# ATmega324PB_Xplained_Pro_Target_MCU.net
KiCad netlist of a schematic drawn in Altium Designer
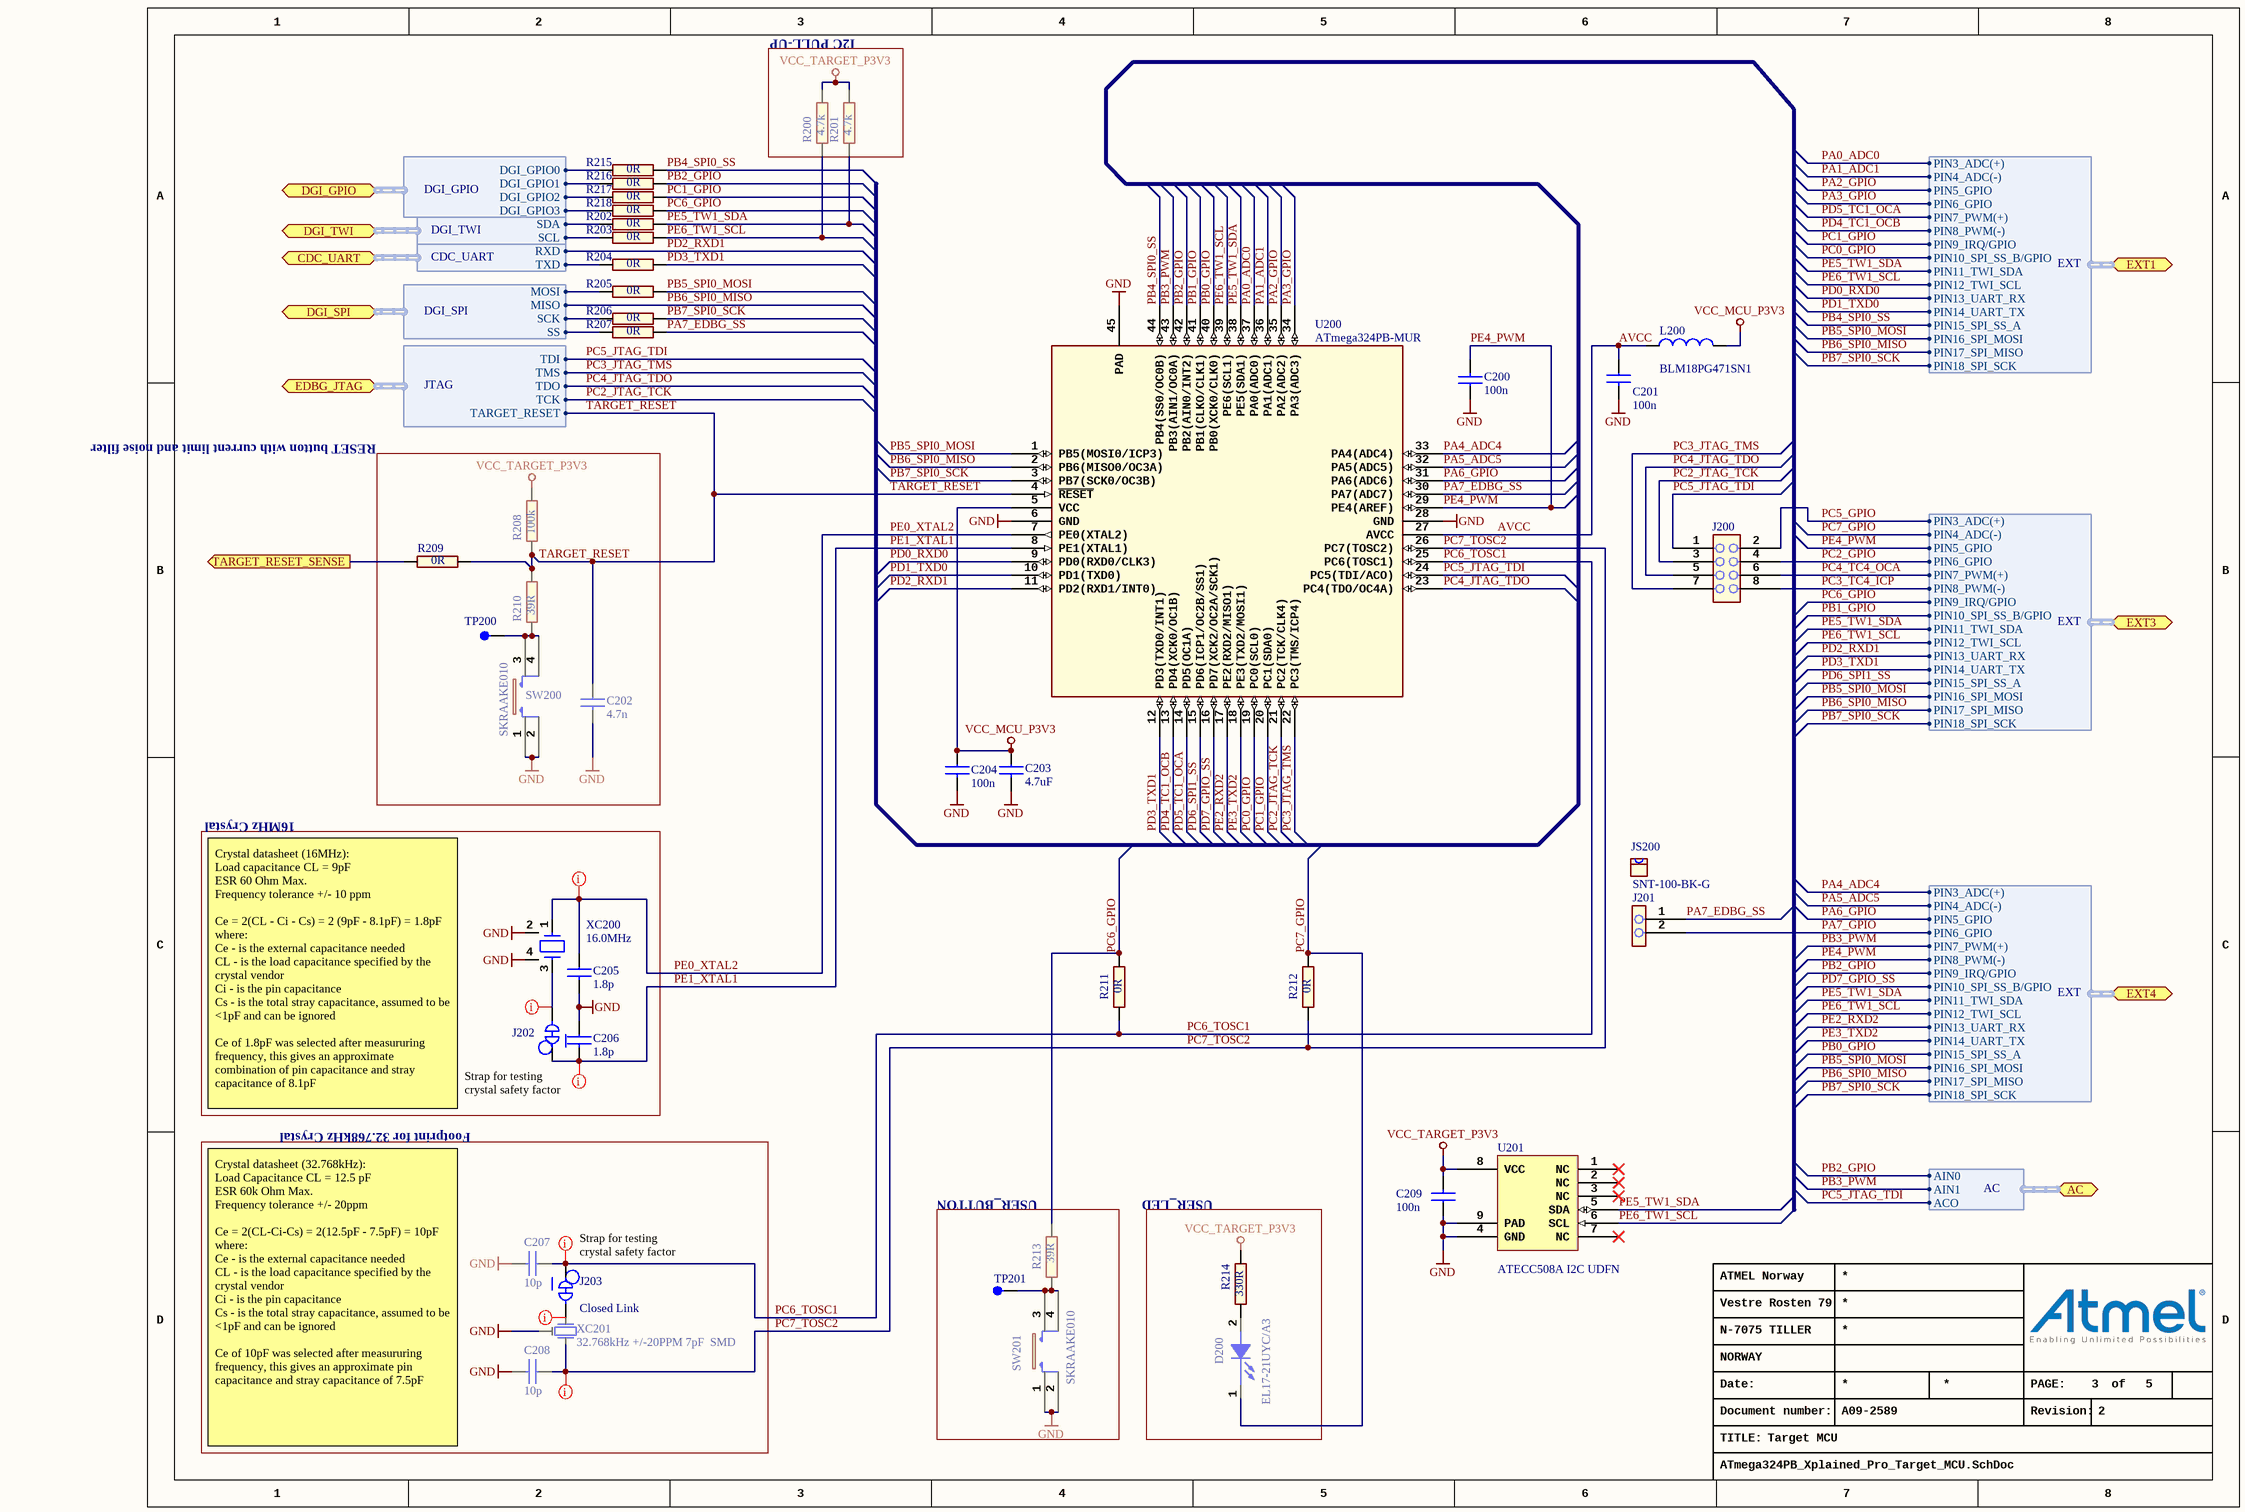
[diagram p0: ATmega324PB_Xplained_Pro_Target_MCU.SchDoc]

(export (version "E")
  (design (tool "Eeschema 10.0.6"))
  (components
    (comp (ref "C200")
      (value "100n")
      (footprint "AP1-00001")
      (description "Ceramic capacitor, SMD 0402, X7R, 16V, +/-10%")
      (fields (field (name "TOLERANCE") "16V, +/-10%") (field (name "MANUFACTURER") "Kemet"))
      (libsource (lib "AltiumDbLib") (part "CAP-NONPOL"))
    )
    (comp (ref "C201")
      (value "100n")
      (footprint "AP1-00001")
      (description "Ceramic capacitor, SMD 0402, X7R, 16V, +/-10%")
      (fields (field (name "TOLERANCE") "16V, +/-10%") (field (name "MANUFACTURER") "Kemet"))
      (libsource (lib "AltiumDbLib") (part "CAP-NONPOL"))
    )
    (comp (ref "C202")
      (value "4.7n")
      (footprint "AP1-00053")
      (description "Ceramic capacitor, SMD 0402, X7R, 25V, +/-10% (de35287)")
      (fields (field (name "TOLERANCE") "25V, +/-10%"))
      (libsource (lib "AltiumDbLib") (part "CAP-NONPOL"))
    )
    (comp (ref "C203")
      (value "4.7uF")
      (footprint "AP1-00039")
      (description "Ceramic capacitor, SMD 0603, X5R, 10V, 10% (de31036)")
      (fields (field (name "MANUFACTURER") "tdk") (field (name "MPN") "C1608X5R1A475K"))
      (libsource (lib "AltiumDbLib") (part "CAP-NONPOL"))
    )
    (comp (ref "C204")
      (value "100n")
      (footprint "AP1-00001")
      (description "Ceramic capacitor, SMD 0402, X7R, 16V, +/-10%")
      (fields (field (name "TOLERANCE") "16V, +/-10%") (field (name "MANUFACTURER") "Kemet"))
      (libsource (lib "AltiumDbLib") (part "CAP-NONPOL"))
    )
    (comp (ref "C205")
      (value "1.8p")
      (footprint "AP1-00001")
      (description "Ceramic capacitor, SMD 0402, NP0, 50V, +/-0.25pF")
      (fields (field (name "TOLERANCE") "50V, +/-0.25pF"))
      (libsource (lib "AltiumDbLib") (part "CAP-NONPOL"))
    )
    (comp (ref "C206")
      (value "1.8p")
      (footprint "AP1-00001")
      (description "Ceramic capacitor, SMD 0402, NP0, 50V, +/-0.25pF")
      (fields (field (name "TOLERANCE") "50V, +/-0.25pF"))
      (libsource (lib "AltiumDbLib") (part "CAP-NONPOL"))
    )
    (comp (ref "C207")
      (value "10p")
      (footprint "AP1-00001")
      (description "Ceramic capacitor, SMD 0402, NP0, 50V, +/-5%")
      (fields (field (name "TOLERANCE") "50V, +/-5%"))
      (libsource (lib "AltiumDbLib") (part "CAP-NONPOL"))
    )
    (comp (ref "C208")
      (value "10p")
      (footprint "AP1-00001")
      (description "Ceramic capacitor, SMD 0402, NP0, 50V, +/-5%")
      (fields (field (name "TOLERANCE") "50V, +/-5%"))
      (libsource (lib "AltiumDbLib") (part "CAP-NONPOL"))
    )
    (comp (ref "C209")
      (value "100n")
      (footprint "AP1-00001")
      (description "Ceramic capacitor, SMD 0402, X7R, 16V, +/-10%")
      (fields (field (name "TOLERANCE") "16V, +/-10%") (field (name "MANUFACTURER") "Kemet"))
      (libsource (lib "AltiumDbLib") (part "CAP-NONPOL"))
    )
    (comp (ref "D200")
      (value "EL17-21UYC/A3")
      (footprint "AP4-00013")
      (description "LED, Yellow, Wave length=591nm, SMD 0805, ±70°")
      (fields (field (name "MANUFACTURER") "Everlight") (field (name "MPN") "17-21UYC/S530-A3/TR8"))
      (libsource (lib "AltiumDbLib") (part "LED_12"))
    )
    (comp (ref "J200")
      (value "~")
      (footprint "AP8-00971")
      (description "2x4 pin header, 2.54 mm pitch, Pin-in-Paste THM")
      (fields (field (name "MANUFACTURER") "SAMTEC") (field (name "MPN") "HMTSW-104-23-F-D-237"))
      (libsource (lib "AltiumDbLib") (part "HEADER 2x4"))
    )
    (comp (ref "J201")
      (value "~")
      (footprint "AP8-00733")
      (description "1x2 pin header, 2.54mm pitch, Pin-in-Paste THM")
      (fields (field (name "MANUFACTURER") "SAMTEC") (field (name "MPN") "HMTSW-102-23-F-S-237"))
      (libsource (lib "AltiumDbLib") (part "HEADER 1x2"))
    )
    (comp (ref "J202")
      (value "~")
      (footprint "AP8-00595")
      (description "Closed Link 0402")
      (libsource (lib "AltiumDbLib") (part "SMD-STRAP_CLOSED"))
    )
    (comp (ref "J203")
      (value "Closed Link")
      (footprint "AP8-00595")
      (description "Closed Link 0402")
      (libsource (lib "AltiumDbLib") (part "SMD-STRAP_CLOSED"))
    )
    (comp (ref "JS200")
      (value "SNT-100-BK-G")
      (footprint "AP8-00525")
      (description "Jumper cap for 2.54mm pinheader")
      (fields (field (name "MANUFACTURER") "SAMTEC"))
      (libsource (lib "AltiumDbLib") (part "JUMPER_CAP"))
    )
    (comp (ref "L200")
      (value "BLM18PG471SN1")
      (footprint "AP3-00005")
      (description "SMD RF inductor 0603. Z=470Ohm (@100MHz), Max R(dc)=0.65Ohm, Max current=1A")
      (fields (field (name "TOLERANCE") "±25%") (field (name "MANUFACTURER") "Murata"))
      (libsource (lib "AltiumDbLib") (part "INDUCTOR"))
    )
    (comp (ref "R200")
      (value "4.7k")
      (footprint "AP2-00000")
      (description "Thick film resistor, SMD 0402, 1/16W, 1%")
      (fields (field (name "TOLERANCE") "1 %"))
      (libsource (lib "") (part "R2_2"))
    )
    (comp (ref "R201")
      (value "4.7k")
      (footprint "AP2-00000")
      (description "Thick film resistor, SMD 0402, 1/16W, 1%")
      (fields (field (name "TOLERANCE") "1 %"))
      (libsource (lib "") (part "R2_2"))
    )
    (comp (ref "R202")
      (value "0R")
      (footprint "AP2-00000")
      (description "RES 0.0 OHM 1/16W 0402 SMD")
      (fields (field (name "TOLERANCE") "1 %") (field (name "MANUFACTURER") "(n/a)"))
      (libsource (lib "AltiumDbLib") (part "R2"))
    )
    (comp (ref "R203")
      (value "0R")
      (footprint "AP2-00000")
      (description "RES 0.0 OHM 1/16W 0402 SMD")
      (fields (field (name "TOLERANCE") "1 %") (field (name "MANUFACTURER") "(n/a)"))
      (libsource (lib "AltiumDbLib") (part "R2"))
    )
    (comp (ref "R204")
      (value "0R")
      (footprint "AP2-00000")
      (description "RES 0.0 OHM 1/16W 0402 SMD")
      (fields (field (name "TOLERANCE") "1 %") (field (name "MANUFACTURER") "(n/a)"))
      (libsource (lib "AltiumDbLib") (part "R2"))
    )
    (comp (ref "R205")
      (value "0R")
      (footprint "AP2-00000")
      (description "RES 0.0 OHM 1/16W 0402 SMD")
      (fields (field (name "TOLERANCE") "1 %") (field (name "MANUFACTURER") "(n/a)"))
      (libsource (lib "AltiumDbLib") (part "R2"))
    )
    (comp (ref "R206")
      (value "0R")
      (footprint "AP2-00000")
      (description "RES 0.0 OHM 1/16W 0402 SMD")
      (fields (field (name "TOLERANCE") "1 %") (field (name "MANUFACTURER") "(n/a)"))
      (libsource (lib "AltiumDbLib") (part "R2"))
    )
    (comp (ref "R207")
      (value "0R")
      (footprint "AP2-00000")
      (description "RES 0.0 OHM 1/16W 0402 SMD")
      (fields (field (name "TOLERANCE") "1 %") (field (name "MANUFACTURER") "(n/a)"))
      (libsource (lib "AltiumDbLib") (part "R2"))
    )
    (comp (ref "R208")
      (value "100k")
      (footprint "AP2-00011")
      (description "Thick film resistor, SMD 0402, 1/16W, 1%")
      (fields (field (name "TOLERANCE") "1 %"))
      (libsource (lib "") (part "R2_2"))
    )
    (comp (ref "R209")
      (value "0R")
      (footprint "AP2-00000")
      (description "RES 0.0 OHM 1/16W 0402 SMD")
      (fields (field (name "TOLERANCE") "1 %") (field (name "MANUFACTURER") "(n/a)"))
      (libsource (lib "AltiumDbLib") (part "R2"))
    )
    (comp (ref "R210")
      (value "39R")
      (footprint "AP2-00011")
      (description "Thick film resistor, SMD 0402, 1/16W, 1%")
      (fields (field (name "TOLERANCE") "1 %"))
      (libsource (lib "") (part "R2_1"))
    )
    (comp (ref "R211")
      (value "0R")
      (footprint "AP2-00000")
      (description "RES 0.0 OHM 1/16W 0402 SMD")
      (fields (field (name "TOLERANCE") "1 %") (field (name "MANUFACTURER") "(n/a)"))
      (libsource (lib "") (part "R2_2"))
    )
    (comp (ref "R212")
      (value "0R")
      (footprint "AP2-00000")
      (description "RES 0.0 OHM 1/16W 0402 SMD")
      (fields (field (name "TOLERANCE") "1 %") (field (name "MANUFACTURER") "(n/a)"))
      (libsource (lib "") (part "R2_2"))
    )
    (comp (ref "R213")
      (value "39R")
      (footprint "AP2-00011")
      (description "Thick film resistor, SMD 0402, 1/16W, 1%")
      (fields (field (name "TOLERANCE") "1 %"))
      (libsource (lib "") (part "R2_1"))
    )
    (comp (ref "R214")
      (value "330R")
      (footprint "AP2-00000")
      (description "Thick film resistor, SMD 0402, 1/16W, 1%")
      (fields (field (name "TOLERANCE") "1 %"))
      (libsource (lib "") (part "R2_2"))
    )
    (comp (ref "R215")
      (value "0R")
      (footprint "AP2-00000")
      (description "RES 0.0 OHM 1/16W 0402 SMD")
      (fields (field (name "TOLERANCE") "1 %") (field (name "MANUFACTURER") "(n/a)"))
      (libsource (lib "AltiumDbLib") (part "R2"))
    )
    (comp (ref "R216")
      (value "0R")
      (footprint "AP2-00000")
      (description "RES 0.0 OHM 1/16W 0402 SMD")
      (fields (field (name "TOLERANCE") "1 %") (field (name "MANUFACTURER") "(n/a)"))
      (libsource (lib "AltiumDbLib") (part "R2"))
    )
    (comp (ref "R217")
      (value "0R")
      (footprint "AP2-00000")
      (description "RES 0.0 OHM 1/16W 0402 SMD")
      (fields (field (name "TOLERANCE") "1 %") (field (name "MANUFACTURER") "(n/a)"))
      (libsource (lib "AltiumDbLib") (part "R2"))
    )
    (comp (ref "R218")
      (value "0R")
      (footprint "AP2-00000")
      (description "RES 0.0 OHM 1/16W 0402 SMD")
      (fields (field (name "TOLERANCE") "1 %") (field (name "MANUFACTURER") "(n/a)"))
      (libsource (lib "AltiumDbLib") (part "R2"))
    )
    (comp (ref "SW200")
      (value "SKRAAKE010")
      (footprint "AP8-00137")
      (description "6.2x6.2 mm SMD tact switch, same as A08-0091 but less force is needed")
      (fields
        (field (name "MANUFACTURER") "ALPS")
        (field (name "Comment") "Can be ordered in low volumes from Mouser")
      )
      (libsource (lib "AltiumDbLib") (part "PUSHBUTTON1"))
    )
    (comp (ref "SW201")
      (value "SKRAAKE010")
      (footprint "AP8-00137")
      (description "6.2x6.2 mm SMD tact switch, same as A08-0091 but less force is needed")
      (fields
        (field (name "MANUFACTURER") "ALPS")
        (field (name "Comment") "Can be ordered in low volumes from Mouser")
      )
      (libsource (lib "AltiumDbLib") (part "PUSHBUTTON1"))
    )
    (comp (ref "TP200")
      (value "~")
      (footprint "AP8-00010")
      (description "Single SMD testpad")
      (libsource (lib "AltiumDbLib") (part "TESTPOINT"))
    )
    (comp (ref "TP201")
      (value "~")
      (footprint "AP8-00010")
      (description "Single SMD testpad")
      (libsource (lib "AltiumDbLib") (part "TESTPOINT"))
    )
    (comp (ref "U200")
      (value "ATmega324PB-MUR")
      (footprint "AP6-00147")
      (description "AVR 8-bit RISC MCU")
      (fields
        (field (name "MANUFACTURER") "ATMEL")
        (field (name "Comment") "Footprint has tight silkscreen to solder mask expansion clearance")
      )
      (libsource (lib "AltiumDbLib") (part "ATmega324PB"))
    )
    (comp (ref "U201")
      (value "ATECC508A I2C UDFN")
      (footprint "AP6-00409")
      (description "ATECC508A with an I2C Interface and a 8 Pin UDFN Package with Paddle")
      (fields (field (name "MANUFACTURER") "ATMEL") (field (name "MPN") "ATECC508A-MAHDA-T"))
      (libsource (lib "AltiumDbLib") (part "ATECC508A_I2C_UDFN"))
    )
    (comp (ref "XC200")
      (value "16.0MHz")
      (footprint "AP7-00061")
      (description "16MHz uXtal, 3.2 x 2.5 mm SMD, CL=9pF, 15PPM, ESR=80ohm(Max.")
      (fields (field (name "TOLERANCE") "15ppm") (field (name "MANUFACTURER") "Epson Toyocom"))
      (libsource (lib "AltiumDbLib") (part "TSX-3225"))
    )
    (comp (ref "XC201")
      (value "32.768kHz +/-20PPM 7pF  SMD")
      (footprint "AP7-00044")
      (description "32k768 crystal, +-20ppm, CL=7pF, max ESR 60kOhm, SMD")
      (fields (field (name "TOLERANCE") "+/- 20 PPM") (field (name "MANUFACTURER") "Micro Crystal"))
      (libsource (lib "AltiumDbLib") (part "CRYSTAL_2P_metal"))
    )
  )
  (nets
    (net (code "8") (name "/AVCC") (class "Default")
      (node (ref "C201") (pin "1") (pinfunction "1_1") (pintype "passive"))
      (node (ref "L200") (pin "1") (pinfunction "1_1") (pintype "passive"))
      (node (ref "U200") (pin "27") (pinfunction "AVCC_27") (pintype "power_in"))
    )
    (net (code "10") (name "/PA0_ADC0") (class "Default")
      (node (ref "U200") (pin "37") (pinfunction "PA0(ADC0)_37") (pintype "bidirectional"))
    )
    (net (code "11") (name "/PA1_ADC1") (class "Default")
      (node (ref "U200") (pin "36") (pinfunction "PA1(ADC1)_36") (pintype "bidirectional"))
    )
    (net (code "12") (name "/PA2_GPIO") (class "Default")
      (node (ref "U200") (pin "35") (pinfunction "PA2(ADC2)_35") (pintype "bidirectional"))
    )
    (net (code "13") (name "/PA3_GPIO") (class "Default")
      (node (ref "U200") (pin "34") (pinfunction "PA3(ADC3)_34") (pintype "bidirectional"))
    )
    (net (code "14") (name "/PA4_ADC4") (class "Default")
      (node (ref "U200") (pin "33") (pinfunction "PA4(ADC4)_33") (pintype "bidirectional"))
    )
    (net (code "15") (name "/PA5_ADC5") (class "Default")
      (node (ref "U200") (pin "32") (pinfunction "PA5(ADC5)_32") (pintype "bidirectional"))
    )
    (net (code "16") (name "/PA6_GPIO") (class "Default")
      (node (ref "U200") (pin "31") (pinfunction "PA6(ADC6)_31") (pintype "bidirectional"))
    )
    (net (code "17") (name "/PA7_EDBG_SS") (class "Default")
      (node (ref "J201") (pin "1") (pinfunction "1_1") (pintype "passive"))
      (node (ref "R207") (pin "2") (pinfunction "2_2") (pintype "passive"))
      (node (ref "U200") (pin "30") (pinfunction "PA7(ADC7)_30") (pintype "bidirectional"))
    )
    (net (code "18") (name "/PA7_GPIO") (class "Default")
      (node (ref "J201") (pin "2") (pinfunction "2_2") (pintype "passive"))
    )
    (net (code "19") (name "/PB0_GPIO") (class "Default")
      (node (ref "U200") (pin "40") (pinfunction "PB0(XCK0/CLK0)_40") (pintype "bidirectional"))
    )
    (net (code "20") (name "/PB1_GPIO") (class "Default")
      (node (ref "U200") (pin "41") (pinfunction "PB1(CLKO/CLK1)_41") (pintype "bidirectional"))
    )
    (net (code "21") (name "/PB2_GPIO") (class "Default")
      (node (ref "R216") (pin "2") (pinfunction "2_2") (pintype "passive"))
      (node (ref "U200") (pin "42") (pinfunction "PB2(AIN0/INT2)_42") (pintype "bidirectional"))
    )
    (net (code "22") (name "/PB3_PWM") (class "Default")
      (node (ref "U200") (pin "43") (pinfunction "PB3(AIN1/OC0A)_43") (pintype "bidirectional"))
    )
    (net (code "23") (name "/PB4_SPI0_SS") (class "Default")
      (node (ref "R215") (pin "2") (pinfunction "2_2") (pintype "passive"))
      (node (ref "U200") (pin "44") (pinfunction "PB4(SS0/OC0B)_44") (pintype "bidirectional"))
    )
    (net (code "24") (name "/PB5_SPI0_MOSI") (class "Default")
      (node (ref "R205") (pin "2") (pinfunction "2_2") (pintype "passive"))
      (node (ref "U200") (pin "1") (pinfunction "PB5(MOSI0/ICP3)_1") (pintype "bidirectional"))
    )
    (net (code "25") (name "/PB6_SPI0_MISO") (class "Default")
      (node (ref "U200") (pin "2") (pinfunction "PB6(MISO0/OC3A)_2") (pintype "bidirectional"))
    )
    (net (code "26") (name "/PB7_SPI0_SCK") (class "Default")
      (node (ref "R206") (pin "2") (pinfunction "2_2") (pintype "passive"))
      (node (ref "U200") (pin "3") (pinfunction "PB7(SCK0/OC3B)_3") (pintype "bidirectional"))
    )
    (net (code "27") (name "/PC0_GPIO") (class "Default")
      (node (ref "U200") (pin "19") (pinfunction "PC0(SCL0)_19") (pintype "bidirectional"))
    )
    (net (code "28") (name "/PC1_GPIO") (class "Default")
      (node (ref "R217") (pin "2") (pinfunction "2_2") (pintype "passive"))
      (node (ref "U200") (pin "20") (pinfunction "PC1(SDA0)_20") (pintype "bidirectional"))
    )
    (net (code "29") (name "/PC2_GPIO") (class "Default")
      (node (ref "J200") (pin "4") (pinfunction "4_4") (pintype "passive"))
    )
    (net (code "30") (name "/PC2_JTAG_TCK") (class "Default")
      (node (ref "J200") (pin "3") (pinfunction "3_3") (pintype "passive"))
      (node (ref "U200") (pin "21") (pinfunction "PC2(TCK/CLK4)_21") (pintype "bidirectional"))
    )
    (net (code "31") (name "/PC3_JTAG_TMS") (class "Default")
      (node (ref "J200") (pin "7") (pinfunction "7_7") (pintype "passive"))
      (node (ref "U200") (pin "22") (pinfunction "PC3(TMS/ICP4)_22") (pintype "bidirectional"))
    )
    (net (code "32") (name "/PC3_TC4_ICP") (class "Default")
      (node (ref "J200") (pin "8") (pinfunction "8_8") (pintype "passive"))
    )
    (net (code "33") (name "/PC4_JTAG_TDO") (class "Default")
      (node (ref "J200") (pin "5") (pinfunction "5_5") (pintype "passive"))
      (node (ref "U200") (pin "23") (pinfunction "PC4(TDO/OC4A)_23") (pintype "bidirectional"))
    )
    (net (code "34") (name "/PC4_TC4_OCA") (class "Default")
      (node (ref "J200") (pin "6") (pinfunction "6_6") (pintype "passive"))
    )
    (net (code "35") (name "/PC5_GPIO") (class "Default")
      (node (ref "J200") (pin "2") (pinfunction "2_2") (pintype "passive"))
    )
    (net (code "36") (name "/PC5_JTAG_TDI") (class "Default")
      (node (ref "J200") (pin "1") (pinfunction "1_1") (pintype "passive"))
      (node (ref "U200") (pin "24") (pinfunction "PC5(TDI/ACO)_24") (pintype "bidirectional"))
    )
    (net (code "37") (name "/PC6_GPIO") (class "Default")
      (node (ref "R211") (pin "2") (pinfunction "2_2") (pintype "passive"))
      (node (ref "R213") (pin "2") (pinfunction "2_2") (pintype "passive"))
      (node (ref "R218") (pin "2") (pinfunction "2_2") (pintype "passive"))
    )
    (net (code "38") (name "/PC6_TOSC1") (class "Default")
      (node (ref "C207") (pin "1") (pinfunction "1_1") (pintype "passive"))
      (node (ref "J203") (pin "1") (pinfunction "1_1") (pintype "passive"))
      (node (ref "R211") (pin "1") (pinfunction "1_1") (pintype "passive"))
      (node (ref "U200") (pin "25") (pinfunction "PC6(TOSC1)_25") (pintype "bidirectional"))
    )
    (net (code "39") (name "/PC7_GPIO") (class "Default")
      (node (ref "D200") (pin "1") (pinfunction "CATHODE_1") (pintype "passive"))
      (node (ref "R212") (pin "2") (pinfunction "2_2") (pintype "passive"))
    )
    (net (code "40") (name "/PC7_TOSC2") (class "Default")
      (node (ref "C208") (pin "1") (pinfunction "1_1") (pintype "passive"))
      (node (ref "R212") (pin "1") (pinfunction "1_1") (pintype "passive"))
      (node (ref "U200") (pin "26") (pinfunction "PC7(TOSC2)_26") (pintype "bidirectional"))
      (node (ref "XC201") (pin "1") (pinfunction "1_1") (pintype "passive"))
    )
    (net (code "41") (name "/PD0_RXD0") (class "Default")
      (node (ref "U200") (pin "9") (pinfunction "PD0(RXD0/CLK3)_9") (pintype "bidirectional"))
    )
    (net (code "42") (name "/PD1_TXD0") (class "Default")
      (node (ref "U200") (pin "10") (pinfunction "PD1(TXD0)_10") (pintype "bidirectional"))
    )
    (net (code "43") (name "/PD2_RXD1") (class "Default")
      (node (ref "U200") (pin "11") (pinfunction "PD2(RXD1/INT0)_11") (pintype "bidirectional"))
    )
    (net (code "44") (name "/PD3_TXD1") (class "Default")
      (node (ref "R204") (pin "2") (pinfunction "2_2") (pintype "passive"))
      (node (ref "U200") (pin "12") (pinfunction "PD3(TXD0/INT1)_12") (pintype "bidirectional"))
    )
    (net (code "45") (name "/PD4_TC1_OCB") (class "Default")
      (node (ref "U200") (pin "13") (pinfunction "PD4(XCK0/OC1B)_13") (pintype "bidirectional"))
    )
    (net (code "46") (name "/PD5_TC1_OCA") (class "Default")
      (node (ref "U200") (pin "14") (pinfunction "PD5(OC1A)_14") (pintype "bidirectional"))
    )
    (net (code "47") (name "/PD6_SPI1_SS") (class "Default")
      (node (ref "U200") (pin "15") (pinfunction "PD6(ICP1/OC2B/SS1)_15") (pintype "bidirectional"))
    )
    (net (code "48") (name "/PD7_GPIO_SS") (class "Default")
      (node (ref "U200") (pin "16") (pinfunction "PD7(XCK2/OC2A/SCK1)_16") (pintype "bidirectional"))
    )
    (net (code "49") (name "/PE0_XTAL2") (class "Default")
      (node (ref "C205") (pin "1") (pinfunction "1_1") (pintype "passive"))
      (node (ref "U200") (pin "7") (pinfunction "PE0(XTAL2)_7") (pintype "output"))
      (node (ref "XC200") (pin "1") (pinfunction "IN_1") (pintype "passive"))
    )
    (net (code "50") (name "/PE1_XTAL1") (class "Default")
      (node (ref "C206") (pin "2") (pinfunction "2_2") (pintype "passive"))
      (node (ref "J202") (pin "1") (pinfunction "1_1") (pintype "passive"))
      (node (ref "U200") (pin "8") (pinfunction "PE1(XTAL1)_8") (pintype "input"))
    )
    (net (code "51") (name "/PE2_RXD2") (class "Default")
      (node (ref "U200") (pin "17") (pinfunction "PE2(RXD2/MISO1)_17") (pintype "bidirectional"))
    )
    (net (code "52") (name "/PE3_TXD2") (class "Default")
      (node (ref "U200") (pin "18") (pinfunction "PE3(TXD2/MOSI1)_18") (pintype "bidirectional"))
    )
    (net (code "53") (name "/PE4_PWM") (class "Default")
      (node (ref "C200") (pin "2") (pinfunction "2_2") (pintype "passive"))
      (node (ref "U200") (pin "29") (pinfunction "PE4(AREF)_29") (pintype "bidirectional"))
    )
    (net (code "54") (name "/PE5_TW1_SDA") (class "Default")
      (node (ref "R201") (pin "1") (pinfunction "1_1") (pintype "passive"))
      (node (ref "R202") (pin "2") (pinfunction "2_2") (pintype "passive"))
      (node (ref "U200") (pin "38") (pinfunction "PE5(SDA1)_38") (pintype "bidirectional"))
      (node (ref "U201") (pin "5") (pinfunction "SDA_5") (pintype "bidirectional"))
    )
    (net (code "55") (name "/PE6_TW1_SCL") (class "Default")
      (node (ref "R200") (pin "1") (pinfunction "1_1") (pintype "passive"))
      (node (ref "R203") (pin "2") (pinfunction "2_2") (pintype "passive"))
      (node (ref "U200") (pin "39") (pinfunction "PE6(SCL1)_39") (pintype "bidirectional"))
      (node (ref "U201") (pin "6") (pinfunction "SCL_6") (pintype "input"))
    )
    (net (code "56") (name "/TARGET_RESET") (class "Default")
      (node (ref "C202") (pin "1") (pinfunction "1_1") (pintype "passive"))
      (node (ref "R208") (pin "1") (pinfunction "1_1") (pintype "passive"))
      (node (ref "R209") (pin "2") (pinfunction "2_2") (pintype "passive"))
      (node (ref "R210") (pin "2") (pinfunction "2_2") (pintype "passive"))
      (node (ref "U200") (pin "4") (pinfunction "~{RESET}_4") (pintype "input"))
    )
    (net (code "57") (name "/TARGET_RESET_SENSE") (class "Default")
      (node (ref "R209") (pin "1") (pinfunction "1_1") (pintype "passive"))
    )
    (net (code "64") (name "GND") (class "Default")
      (node (ref "C200") (pin "1") (pinfunction "1_1") (pintype "passive"))
      (node (ref "C201") (pin "2") (pinfunction "2_2") (pintype "passive"))
      (node (ref "C202") (pin "2") (pinfunction "2_2") (pintype "passive"))
      (node (ref "C203") (pin "2") (pinfunction "2_2") (pintype "passive"))
      (node (ref "C204") (pin "2") (pinfunction "2_2") (pintype "passive"))
      (node (ref "C205") (pin "2") (pinfunction "2_2") (pintype "passive"))
      (node (ref "C206") (pin "1") (pinfunction "1_1") (pintype "passive"))
      (node (ref "C207") (pin "2") (pinfunction "2_2") (pintype "passive"))
      (node (ref "C208") (pin "2") (pinfunction "2_2") (pintype "passive"))
      (node (ref "C209") (pin "1") (pinfunction "1_1") (pintype "passive"))
      (node (ref "SW200") (pin "1") (pinfunction "1_1") (pintype "passive"))
      (node (ref "SW200") (pin "2") (pinfunction "2_2") (pintype "passive"))
      (node (ref "SW201") (pin "1") (pinfunction "1_1") (pintype "passive"))
      (node (ref "SW201") (pin "2") (pinfunction "2_2") (pintype "passive"))
      (node (ref "U200") (pin "28") (pinfunction "GND_28") (pintype "power_in"))
      (node (ref "U200") (pin "45") (pinfunction "PAD_45") (pintype "power_in"))
      (node (ref "U200") (pin "6") (pinfunction "GND_6") (pintype "power_in"))
      (node (ref "U201") (pin "4") (pinfunction "GND_4") (pintype "power_in"))
      (node (ref "U201") (pin "9") (pinfunction "PAD_9") (pintype "power_in"))
      (node (ref "XC200") (pin "2") (pinfunction "GND_2") (pintype "passive"))
      (node (ref "XC200") (pin "4") (pinfunction "GND_4") (pintype "passive"))
      (node (ref "XC201") (pin "3") (pinfunction "3_3") (pintype "passive"))
    )
    (net (code "65") (name "Net-(D200-ANODE)") (class "Default")
      (node (ref "D200") (pin "2") (pinfunction "ANODE_2") (pintype "passive"))
      (node (ref "R214") (pin "1") (pinfunction "1_1") (pintype "passive"))
    )
    (net (code "66") (name "Net-(J203-Pad2)") (class "Default")
      (node (ref "J203") (pin "2") (pinfunction "2_2") (pintype "passive"))
      (node (ref "XC201") (pin "2") (pinfunction "2_2") (pintype "passive"))
    )
    (net (code "67") (name "Net-(R210-Pad1)") (class "Default")
      (node (ref "R210") (pin "1") (pinfunction "1_1") (pintype "passive"))
      (node (ref "SW200") (pin "3") (pinfunction "3_3") (pintype "passive"))
      (node (ref "SW200") (pin "4") (pinfunction "4_4") (pintype "passive"))
      (node (ref "TP200") (pin "1") (pinfunction "1_1") (pintype "passive"))
    )
    (net (code "68") (name "Net-(R213-Pad1)") (class "Default")
      (node (ref "R213") (pin "1") (pinfunction "1_1") (pintype "passive"))
      (node (ref "SW201") (pin "3") (pinfunction "3_3") (pintype "passive"))
      (node (ref "SW201") (pin "4") (pinfunction "4_4") (pintype "passive"))
      (node (ref "TP201") (pin "1") (pinfunction "1_1") (pintype "passive"))
    )
    (net (code "69") (name "Net-(XC200-OUT)") (class "Default")
      (node (ref "J202") (pin "2") (pinfunction "2_2") (pintype "passive"))
      (node (ref "XC200") (pin "3") (pinfunction "OUT_3") (pintype "passive"))
    )
    (net (code "70") (name "VCC_MCU_P3V3") (class "Default")
      (node (ref "C203") (pin "1") (pinfunction "1_1") (pintype "passive"))
      (node (ref "C204") (pin "1") (pinfunction "1_1") (pintype "passive"))
      (node (ref "L200") (pin "2") (pinfunction "2_2") (pintype "passive"))
      (node (ref "U200") (pin "5") (pinfunction "VCC_5") (pintype "power_in"))
    )
    (net (code "71") (name "VCC_TARGET_P3V3") (class "Default")
      (node (ref "C209") (pin "2") (pinfunction "2_2") (pintype "passive"))
      (node (ref "R200") (pin "2") (pinfunction "2_2") (pintype "passive"))
      (node (ref "R201") (pin "2") (pinfunction "2_2") (pintype "passive"))
      (node (ref "R208") (pin "2") (pinfunction "2_2") (pintype "passive"))
      (node (ref "R214") (pin "2") (pinfunction "2_2") (pintype "passive"))
      (node (ref "U201") (pin "8") (pinfunction "VCC_8") (pintype "power_in"))
    )
    (net (code "72") (name "unconnected-(R202-Pad1)") (class "Default")
      (node (ref "R202") (pin "1") (pinfunction "1_1") (pintype "passive"))
    )
    (net (code "73") (name "unconnected-(R203-Pad1)") (class "Default")
      (node (ref "R203") (pin "1") (pinfunction "1_1") (pintype "passive"))
    )
    (net (code "74") (name "unconnected-(R204-Pad1)") (class "Default")
      (node (ref "R204") (pin "1") (pinfunction "1_1") (pintype "passive"))
    )
    (net (code "75") (name "unconnected-(R205-Pad1)") (class "Default")
      (node (ref "R205") (pin "1") (pinfunction "1_1") (pintype "passive"))
    )
    (net (code "76") (name "unconnected-(R206-Pad1)") (class "Default")
      (node (ref "R206") (pin "1") (pinfunction "1_1") (pintype "passive"))
    )
    (net (code "77") (name "unconnected-(R207-Pad1)") (class "Default")
      (node (ref "R207") (pin "1") (pinfunction "1_1") (pintype "passive"))
    )
    (net (code "78") (name "unconnected-(R215-Pad1)") (class "Default")
      (node (ref "R215") (pin "1") (pinfunction "1_1") (pintype "passive"))
    )
    (net (code "79") (name "unconnected-(R216-Pad1)") (class "Default")
      (node (ref "R216") (pin "1") (pinfunction "1_1") (pintype "passive"))
    )
    (net (code "80") (name "unconnected-(R217-Pad1)") (class "Default")
      (node (ref "R217") (pin "1") (pinfunction "1_1") (pintype "passive"))
    )
    (net (code "81") (name "unconnected-(R218-Pad1)") (class "Default")
      (node (ref "R218") (pin "1") (pinfunction "1_1") (pintype "passive"))
    )
    (net (code "82") (name "unconnected-(U201-NC-Pad1)") (class "Default")
      (node (ref "U201") (pin "1") (pinfunction "NC_1") (pintype "passive+no_connect"))
    )
    (net (code "83") (name "unconnected-(U201-NC-Pad2)") (class "Default")
      (node (ref "U201") (pin "2") (pinfunction "NC_2") (pintype "passive+no_connect"))
    )
    (net (code "84") (name "unconnected-(U201-NC-Pad3)") (class "Default")
      (node (ref "U201") (pin "3") (pinfunction "NC_3") (pintype "passive+no_connect"))
    )
    (net (code "85") (name "unconnected-(U201-NC-Pad7)") (class "Default")
      (node (ref "U201") (pin "7") (pinfunction "NC_7") (pintype "passive+no_connect"))
    )
  )
)
